# grillupboard.net
KiCad netlist of a schematic drawn in EAGLE
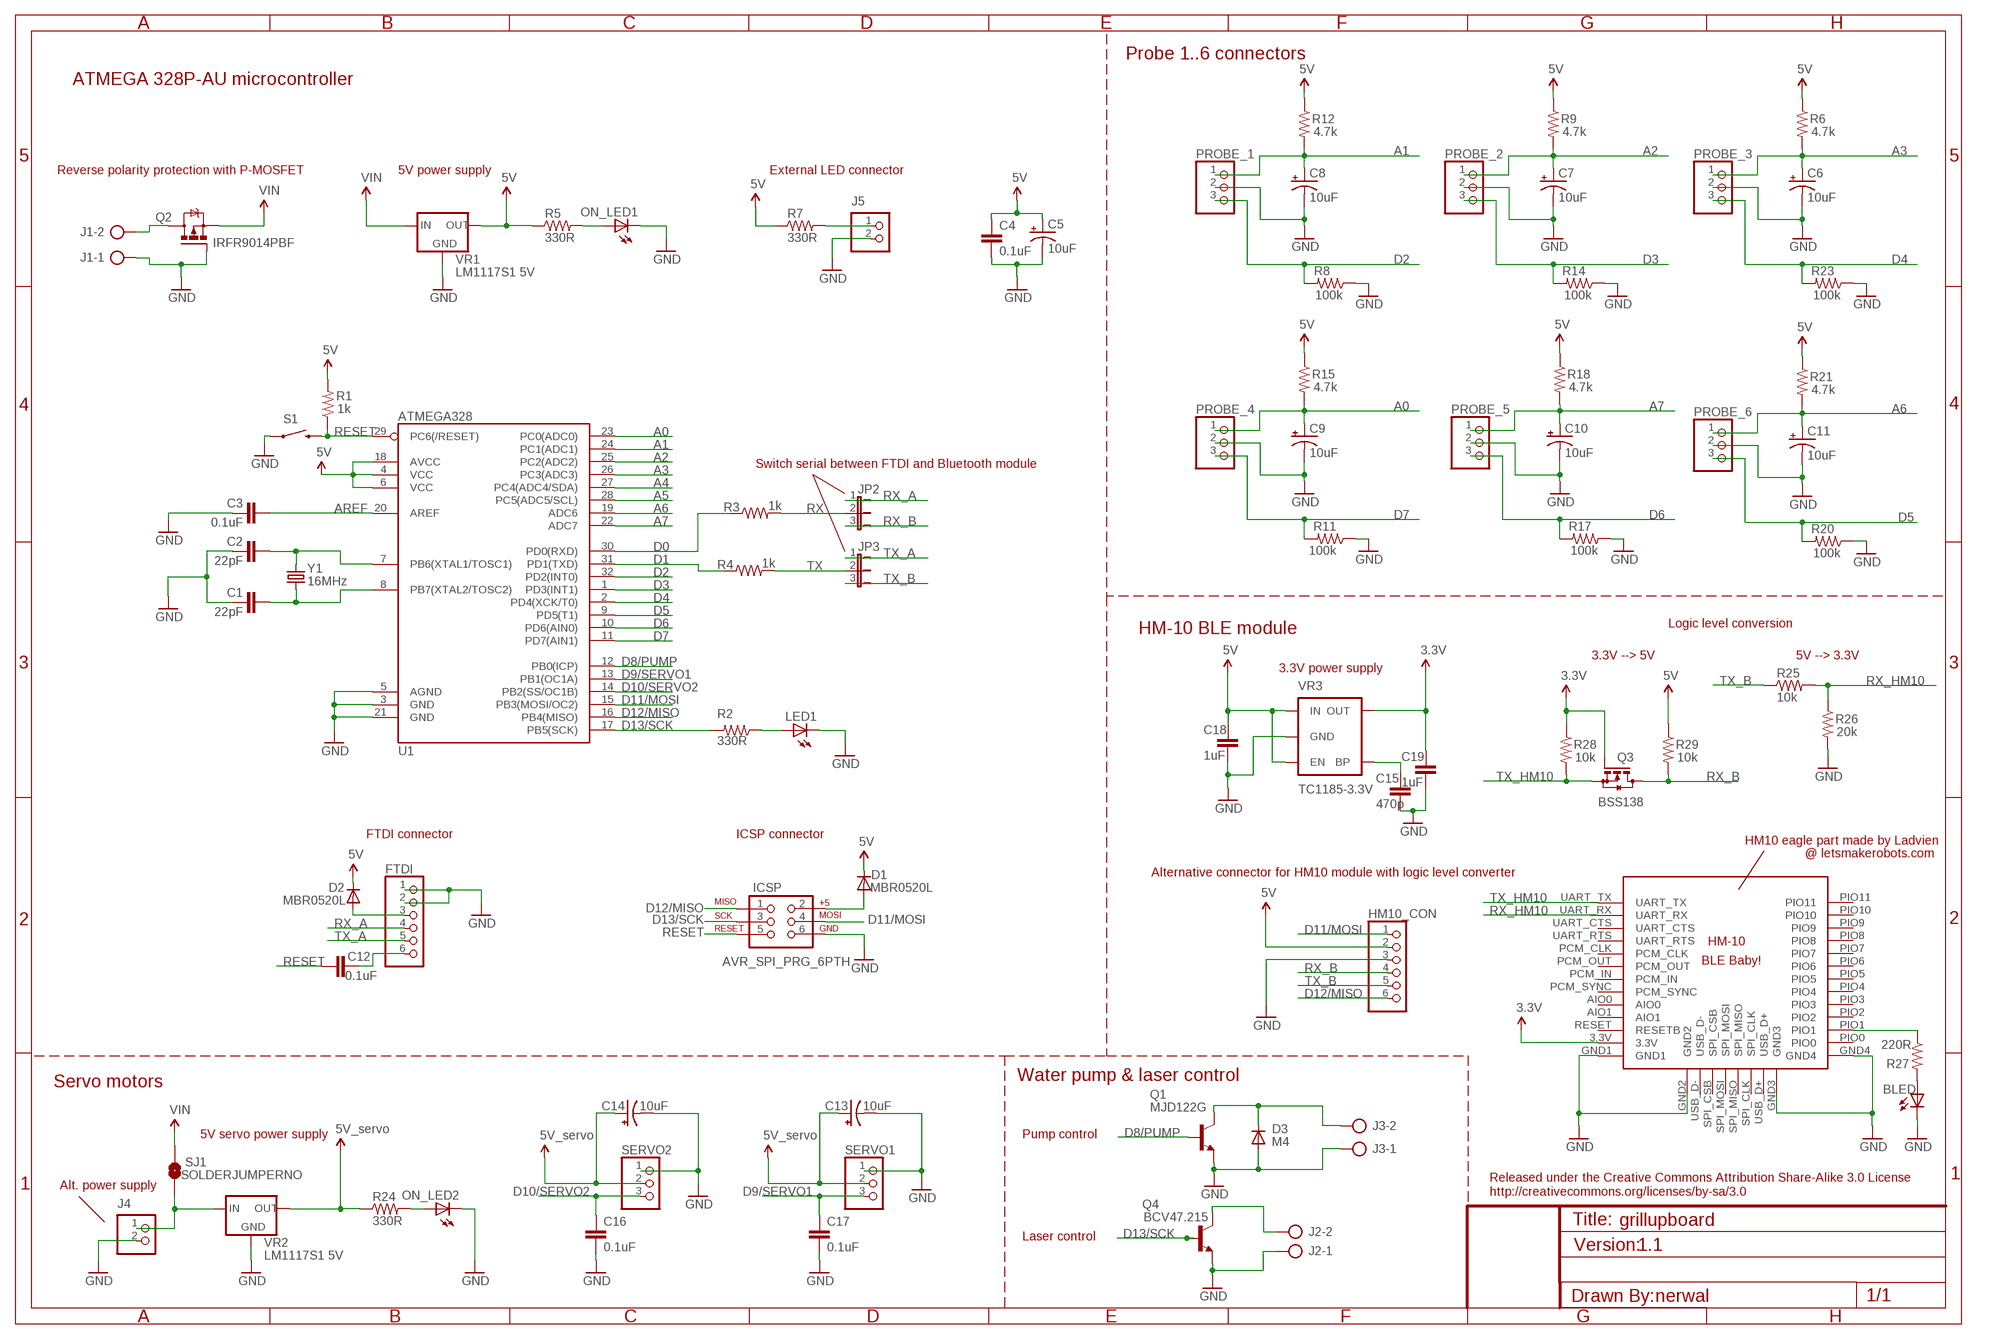
[diagram p0: schematic, sheet 1]

(export (version "E")
  (design (tool "Eeschema 10.0.6"))
  (components
    (comp (ref "BLED")
      (value "LED0603")
      (footprint "eagle-import:LED-0603")
      (libsource (lib "eagle-import") (part "LED0603"))
    )
    (comp (ref "C1")
      (value "22pF")
      (footprint "eagle-import:0805")
      (libsource (lib "eagle-import") (part "CAP0805"))
    )
    (comp (ref "C2")
      (value "22pF")
      (footprint "eagle-import:0805")
      (libsource (lib "eagle-import") (part "CAP0805"))
    )
    (comp (ref "C3")
      (value "0.1uF")
      (footprint "eagle-import:0805")
      (libsource (lib "eagle-import") (part "CAP0805"))
    )
    (comp (ref "C4")
      (value "0.1uF")
      (footprint "eagle-import:0805")
      (libsource (lib "eagle-import") (part "CAP0805"))
    )
    (comp (ref "C5")
      (value "10uF")
      (footprint "eagle-import:EIA3216")
      (libsource (lib "eagle-import") (part "CAP_POL1206"))
    )
    (comp (ref "C6")
      (value "10uF")
      (footprint "eagle-import:EIA3216")
      (libsource (lib "eagle-import") (part "CAP_POL1206"))
    )
    (comp (ref "C7")
      (value "10uF")
      (footprint "eagle-import:EIA3216")
      (libsource (lib "eagle-import") (part "CAP_POL1206"))
    )
    (comp (ref "C8")
      (value "10uF")
      (footprint "eagle-import:EIA3216")
      (libsource (lib "eagle-import") (part "CAP_POL1206"))
    )
    (comp (ref "C9")
      (value "10uF")
      (footprint "eagle-import:EIA3216")
      (libsource (lib "eagle-import") (part "CAP_POL1206"))
    )
    (comp (ref "C10")
      (value "10uF")
      (footprint "eagle-import:EIA3216")
      (libsource (lib "eagle-import") (part "CAP_POL1206"))
    )
    (comp (ref "C11")
      (value "10uF")
      (footprint "eagle-import:EIA3216")
      (libsource (lib "eagle-import") (part "CAP_POL1206"))
    )
    (comp (ref "C12")
      (value "0.1uF")
      (footprint "eagle-import:0805")
      (libsource (lib "eagle-import") (part "CAP0805"))
    )
    (comp (ref "C13")
      (value "10uF")
      (footprint "eagle-import:EIA3216")
      (libsource (lib "eagle-import") (part "CAP_POL1206"))
    )
    (comp (ref "C14")
      (value "10uF")
      (footprint "eagle-import:EIA3216")
      (libsource (lib "eagle-import") (part "CAP_POL1206"))
    )
    (comp (ref "C15")
      (value "470p")
      (footprint "eagle-import:0805")
      (libsource (lib "eagle-import") (part "CAP0805"))
    )
    (comp (ref "C16")
      (value "0.1uF")
      (footprint "eagle-import:0805")
      (libsource (lib "eagle-import") (part "CAP0805"))
    )
    (comp (ref "C17")
      (value "0.1uF")
      (footprint "eagle-import:0805")
      (libsource (lib "eagle-import") (part "CAP0805"))
    )
    (comp (ref "C18")
      (value "1uF")
      (footprint "eagle-import:0805")
      (libsource (lib "eagle-import") (part "CAP0805"))
    )
    (comp (ref "C19")
      (value "1uF")
      (footprint "eagle-import:0805")
      (libsource (lib "eagle-import") (part "CAP0805"))
    )
    (comp (ref "D1")
      (value "MBR0520L")
      (footprint "eagle-import:SOD123")
      (libsource (lib "eagle-import") (part "MBR0520LT"))
    )
    (comp (ref "D2")
      (value "MBR0520L")
      (footprint "eagle-import:SOD123")
      (libsource (lib "eagle-import") (part "MBR0520LT"))
    )
    (comp (ref "D3")
      (value "M4")
      (footprint "eagle-import:SMA-DIODE")
      (libsource (lib "eagle-import") (part "DIODESMA"))
    )
    (comp (ref "FTDI")
      (value "PINHD-1X6")
      (footprint "eagle-import:1X06")
      (libsource (lib "eagle-import") (part "PINHD-1X6"))
    )
    (comp (ref "HM10")
      (value "RANDOM_PARTS_BLE-HM-10")
      (footprint "eagle-import:RANDOM_PARTS_BLE-HM-10")
      (libsource (lib "eagle-import") (part "RANDOM_PARTS_BLE-HM-10"))
    )
    (comp (ref "HM10_CON")
      (value "PINHD-1X6")
      (footprint "eagle-import:1X06")
      (libsource (lib "eagle-import") (part "PINHD-1X6"))
    )
    (comp (ref "ICSP")
      (value "AVR_SPI_PRG_6PTH")
      (footprint "eagle-import:2X3")
      (libsource (lib "eagle-import") (part "AVR_SPI_PRG_6PTH"))
    )
    (comp (ref "J1")
      (value "AK500/2-H")
      (footprint "eagle-import:AK500_2-H")
      (libsource (lib "eagle-import") (part "AK500/2-H"))
    )
    (comp (ref "J2")
      (value "AK500/2-H")
      (footprint "eagle-import:AK500_2-H")
      (libsource (lib "eagle-import") (part "AK500/2-H"))
    )
    (comp (ref "J3")
      (value "AK500/2-H")
      (footprint "eagle-import:AK500_2-H")
      (libsource (lib "eagle-import") (part "AK500/2-H"))
    )
    (comp (ref "J4")
      (value "PINHD-1X2")
      (footprint "eagle-import:1X02")
      (libsource (lib "eagle-import") (part "PINHD-1X2"))
    )
    (comp (ref "J5")
      (value "PINHD-1X2")
      (footprint "eagle-import:1X02")
      (libsource (lib "eagle-import") (part "PINHD-1X2"))
    )
    (comp (ref "JP2")
      (value "JP2E")
      (footprint "eagle-import:JP2")
      (libsource (lib "eagle-import") (part "JP2E"))
    )
    (comp (ref "JP3")
      (value "JP2E")
      (footprint "eagle-import:JP2")
      (libsource (lib "eagle-import") (part "JP2E"))
    )
    (comp (ref "LED1")
      (value "LED0603")
      (footprint "eagle-import:LED-0603")
      (libsource (lib "eagle-import") (part "LED0603"))
    )
    (comp (ref "ON_LED1")
      (value "LED0603")
      (footprint "eagle-import:LED-0603")
      (libsource (lib "eagle-import") (part "LED0603"))
    )
    (comp (ref "ON_LED2")
      (value "LED0603")
      (footprint "eagle-import:LED-0603")
      (libsource (lib "eagle-import") (part "LED0603"))
    )
    (comp (ref "PROBE_1")
      (value "PINHD-1X3")
      (footprint "eagle-import:1X03")
      (libsource (lib "eagle-import") (part "PINHD-1X3"))
    )
    (comp (ref "PROBE_2")
      (value "PINHD-1X3")
      (footprint "eagle-import:1X03")
      (libsource (lib "eagle-import") (part "PINHD-1X3"))
    )
    (comp (ref "PROBE_3")
      (value "PINHD-1X3")
      (footprint "eagle-import:1X03")
      (libsource (lib "eagle-import") (part "PINHD-1X3"))
    )
    (comp (ref "PROBE_4")
      (value "PINHD-1X3")
      (footprint "eagle-import:1X03")
      (libsource (lib "eagle-import") (part "PINHD-1X3"))
    )
    (comp (ref "PROBE_5")
      (value "PINHD-1X3")
      (footprint "eagle-import:1X03")
      (libsource (lib "eagle-import") (part "PINHD-1X3"))
    )
    (comp (ref "PROBE_6")
      (value "PINHD-1X3")
      (footprint "eagle-import:1X03")
      (libsource (lib "eagle-import") (part "PINHD-1X3"))
    )
    (comp (ref "Q1")
      (value "MJD122G")
      (footprint "eagle-import:DPAK")
      (libsource (lib "eagle-import") (part "MJD31"))
    )
    (comp (ref "Q2")
      (value "IRFR9014PBF")
      (footprint "eagle-import:D-PAK_TO252AA")
      (libsource (lib "eagle-import") (part "IRF?5305R"))
    )
    (comp (ref "Q3")
      (value "BSS138")
      (footprint "eagle-import:SOT23")
      (libsource (lib "eagle-import") (part "BSS123"))
    )
    (comp (ref "Q4")
      (value "BCV47.215")
      (footprint "eagle-import:SOT23-BEC")
      (libsource (lib "eagle-import") (part "-NPN-SOT23-BECBCV71"))
    )
    (comp (ref "R1")
      (value "1k")
      (footprint "eagle-import:0805")
      (libsource (lib "eagle-import") (part "RESISTOR0805-RES"))
    )
    (comp (ref "R2")
      (value "330R")
      (footprint "eagle-import:0805")
      (libsource (lib "eagle-import") (part "RESISTOR0805-RES"))
    )
    (comp (ref "R3")
      (value "1k")
      (footprint "eagle-import:0805")
      (libsource (lib "eagle-import") (part "RESISTOR0805-RES"))
    )
    (comp (ref "R4")
      (value "1k")
      (footprint "eagle-import:0805")
      (libsource (lib "eagle-import") (part "RESISTOR0805-RES"))
    )
    (comp (ref "R5")
      (value "330R")
      (footprint "eagle-import:0805")
      (libsource (lib "eagle-import") (part "RESISTOR0805-RES"))
    )
    (comp (ref "R6")
      (value "4.7k")
      (footprint "eagle-import:0805")
      (libsource (lib "eagle-import") (part "RESISTOR0805-RES"))
    )
    (comp (ref "R7")
      (value "330R")
      (footprint "eagle-import:0805")
      (libsource (lib "eagle-import") (part "RESISTOR0805-RES"))
    )
    (comp (ref "R8")
      (value "100k")
      (footprint "eagle-import:0805")
      (libsource (lib "eagle-import") (part "RESISTOR0805-RES"))
    )
    (comp (ref "R9")
      (value "4.7k")
      (footprint "eagle-import:0805")
      (libsource (lib "eagle-import") (part "RESISTOR0805-RES"))
    )
    (comp (ref "R11")
      (value "100k")
      (footprint "eagle-import:0805")
      (libsource (lib "eagle-import") (part "RESISTOR0805-RES"))
    )
    (comp (ref "R12")
      (value "4.7k")
      (footprint "eagle-import:0805")
      (libsource (lib "eagle-import") (part "RESISTOR0805-RES"))
    )
    (comp (ref "R14")
      (value "100k")
      (footprint "eagle-import:0805")
      (libsource (lib "eagle-import") (part "RESISTOR0805-RES"))
    )
    (comp (ref "R15")
      (value "4.7k")
      (footprint "eagle-import:0805")
      (libsource (lib "eagle-import") (part "RESISTOR0805-RES"))
    )
    (comp (ref "R17")
      (value "100k")
      (footprint "eagle-import:0805")
      (libsource (lib "eagle-import") (part "RESISTOR0805-RES"))
    )
    (comp (ref "R18")
      (value "4.7k")
      (footprint "eagle-import:0805")
      (libsource (lib "eagle-import") (part "RESISTOR0805-RES"))
    )
    (comp (ref "R20")
      (value "100k")
      (footprint "eagle-import:0805")
      (libsource (lib "eagle-import") (part "RESISTOR0805-RES"))
    )
    (comp (ref "R21")
      (value "4.7k")
      (footprint "eagle-import:0805")
      (libsource (lib "eagle-import") (part "RESISTOR0805-RES"))
    )
    (comp (ref "R23")
      (value "100k")
      (footprint "eagle-import:0805")
      (libsource (lib "eagle-import") (part "RESISTOR0805-RES"))
    )
    (comp (ref "R24")
      (value "330R")
      (footprint "eagle-import:0805")
      (libsource (lib "eagle-import") (part "RESISTOR0805-RES"))
    )
    (comp (ref "R25")
      (value "10k")
      (footprint "eagle-import:0805")
      (libsource (lib "eagle-import") (part "RESISTOR0805-RES"))
    )
    (comp (ref "R26")
      (value "20k")
      (footprint "eagle-import:0805")
      (libsource (lib "eagle-import") (part "RESISTOR0805-RES"))
    )
    (comp (ref "R27")
      (value "220R")
      (footprint "eagle-import:0805")
      (libsource (lib "eagle-import") (part "RESISTOR0805-RES"))
    )
    (comp (ref "R28")
      (value "10k")
      (footprint "eagle-import:0805")
      (libsource (lib "eagle-import") (part "RESISTOR0805-RES"))
    )
    (comp (ref "R29")
      (value "10k")
      (footprint "eagle-import:0805")
      (libsource (lib "eagle-import") (part "RESISTOR0805-RES"))
    )
    (comp (ref "S1")
      (value "SWITCH-MOMENTARY-2-SMD-1101NE")
      (footprint "eagle-import:TACTILE-SWITCH-1101NE")
      (libsource (lib "eagle-import") (part "SWITCH-MOMENTARY-2-SMD-1101NE"))
    )
    (comp (ref "SERVO1")
      (value "PINHD-1X3")
      (footprint "eagle-import:1X03")
      (libsource (lib "eagle-import") (part "PINHD-1X3"))
    )
    (comp (ref "SERVO2")
      (value "PINHD-1X3")
      (footprint "eagle-import:1X03")
      (libsource (lib "eagle-import") (part "PINHD-1X3"))
    )
    (comp (ref "SJ1")
      (value "SOLDERJUMPERNO")
      (footprint "eagle-import:SJ_2S-NO")
      (libsource (lib "eagle-import") (part "SOLDERJUMPERNO"))
    )
    (comp (ref "U1")
      (value "ATMEGA328")
      (footprint "eagle-import:TQFP32-08")
      (libsource (lib "eagle-import") (part "ATMEGA168"))
    )
    (comp (ref "VR1")
      (value "LM1117S1 5V")
      (footprint "eagle-import:SOT223")
      (libsource (lib "eagle-import") (part "LM1117"))
    )
    (comp (ref "VR2")
      (value "LM1117S1 5V")
      (footprint "eagle-import:SOT223")
      (libsource (lib "eagle-import") (part "LM1117"))
    )
    (comp (ref "VR3")
      (value "TC1185-3.3V")
      (footprint "eagle-import:SOT23-5")
      (libsource (lib "eagle-import") (part "V_REG_LDOSMD"))
    )
    (comp (ref "Y1")
      (value "16MHz")
      (footprint "eagle-import:HC49_S")
      (libsource (lib "eagle-import") (part "CRYSTALHC49S"))
    )
  )
  (nets
    (net (code "1") (name "/A0") (class "Default")
      (node (ref "C9") (pin "A") (pinfunction "+_A") (pintype "passive"))
      (node (ref "PROBE_4") (pin "1") (pinfunction "1_1") (pintype "passive"))
      (node (ref "R15") (pin "2") (pinfunction "2_2") (pintype "passive"))
      (node (ref "U1") (pin "23") (pinfunction "PC0(ADC0)_23") (pintype "bidirectional"))
    )
    (net (code "2") (name "/A1") (class "Default")
      (node (ref "C8") (pin "A") (pinfunction "+_A") (pintype "passive"))
      (node (ref "PROBE_1") (pin "1") (pinfunction "1_1") (pintype "passive"))
      (node (ref "R12") (pin "2") (pinfunction "2_2") (pintype "passive"))
      (node (ref "U1") (pin "24") (pinfunction "PC1(ADC1)_24") (pintype "bidirectional"))
    )
    (net (code "3") (name "/A2") (class "Default")
      (node (ref "C7") (pin "A") (pinfunction "+_A") (pintype "passive"))
      (node (ref "PROBE_2") (pin "1") (pinfunction "1_1") (pintype "passive"))
      (node (ref "R9") (pin "2") (pinfunction "2_2") (pintype "passive"))
      (node (ref "U1") (pin "25") (pinfunction "PC2(ADC2)_25") (pintype "bidirectional"))
    )
    (net (code "4") (name "/A3") (class "Default")
      (node (ref "C6") (pin "A") (pinfunction "+_A") (pintype "passive"))
      (node (ref "PROBE_3") (pin "1") (pinfunction "1_1") (pintype "passive"))
      (node (ref "R6") (pin "2") (pinfunction "2_2") (pintype "passive"))
      (node (ref "U1") (pin "26") (pinfunction "PC3(ADC3)_26") (pintype "bidirectional"))
    )
    (net (code "5") (name "/A4") (class "Default")
      (node (ref "U1") (pin "27") (pinfunction "PC4(ADC4/SDA)_27") (pintype "bidirectional"))
    )
    (net (code "6") (name "/A5") (class "Default")
      (node (ref "U1") (pin "28") (pinfunction "PC5(ADC5/SCL)_28") (pintype "bidirectional"))
    )
    (net (code "7") (name "/A6") (class "Default")
      (node (ref "C11") (pin "A") (pinfunction "+_A") (pintype "passive"))
      (node (ref "PROBE_6") (pin "1") (pinfunction "1_1") (pintype "passive"))
      (node (ref "R21") (pin "2") (pinfunction "2_2") (pintype "passive"))
      (node (ref "U1") (pin "19") (pinfunction "ADC6_19") (pintype "bidirectional"))
    )
    (net (code "8") (name "/A7") (class "Default")
      (node (ref "C10") (pin "A") (pinfunction "+_A") (pintype "passive"))
      (node (ref "PROBE_5") (pin "1") (pinfunction "1_1") (pintype "passive"))
      (node (ref "R18") (pin "2") (pinfunction "2_2") (pintype "passive"))
      (node (ref "U1") (pin "22") (pinfunction "ADC7_22") (pintype "bidirectional"))
    )
    (net (code "9") (name "/AREF") (class "Default")
      (node (ref "C3") (pin "2") (pinfunction "2_2") (pintype "passive"))
      (node (ref "U1") (pin "20") (pinfunction "AREF_20") (pintype "bidirectional"))
    )
    (net (code "10") (name "/D0") (class "Default")
      (node (ref "R3") (pin "1") (pinfunction "1_1") (pintype "passive"))
      (node (ref "U1") (pin "30") (pinfunction "PD0(RXD)_30") (pintype "bidirectional"))
    )
    (net (code "11") (name "/D1") (class "Default")
      (node (ref "R4") (pin "1") (pinfunction "1_1") (pintype "passive"))
      (node (ref "U1") (pin "31") (pinfunction "PD1(TXD)_31") (pintype "bidirectional"))
    )
    (net (code "12") (name "/D2") (class "Default")
      (node (ref "PROBE_1") (pin "3") (pinfunction "3_3") (pintype "passive"))
      (node (ref "R8") (pin "2") (pinfunction "2_2") (pintype "passive"))
      (node (ref "U1") (pin "32") (pinfunction "PD2(INT0)_32") (pintype "bidirectional"))
    )
    (net (code "13") (name "/D3") (class "Default")
      (node (ref "PROBE_2") (pin "3") (pinfunction "3_3") (pintype "passive"))
      (node (ref "R14") (pin "2") (pinfunction "2_2") (pintype "passive"))
      (node (ref "U1") (pin "1") (pinfunction "PD3(INT1)_1") (pintype "bidirectional"))
    )
    (net (code "14") (name "/D4") (class "Default")
      (node (ref "PROBE_3") (pin "3") (pinfunction "3_3") (pintype "passive"))
      (node (ref "R23") (pin "2") (pinfunction "2_2") (pintype "passive"))
      (node (ref "U1") (pin "2") (pinfunction "PD4(XCK/T0)_2") (pintype "bidirectional"))
    )
    (net (code "15") (name "/D5") (class "Default")
      (node (ref "PROBE_6") (pin "3") (pinfunction "3_3") (pintype "passive"))
      (node (ref "R20") (pin "2") (pinfunction "2_2") (pintype "passive"))
      (node (ref "U1") (pin "9") (pinfunction "PD5(T1)_9") (pintype "bidirectional"))
    )
    (net (code "16") (name "/D6") (class "Default")
      (node (ref "PROBE_5") (pin "3") (pinfunction "3_3") (pintype "passive"))
      (node (ref "R17") (pin "2") (pinfunction "2_2") (pintype "passive"))
      (node (ref "U1") (pin "10") (pinfunction "PD6(AIN0)_10") (pintype "bidirectional"))
    )
    (net (code "17") (name "/D7") (class "Default")
      (node (ref "PROBE_4") (pin "3") (pinfunction "3_3") (pintype "passive"))
      (node (ref "R11") (pin "2") (pinfunction "2_2") (pintype "passive"))
      (node (ref "U1") (pin "11") (pinfunction "PD7(AIN1)_11") (pintype "bidirectional"))
    )
    (net (code "18") (name "/D8{slash}PUMP") (class "Default")
      (node (ref "Q1") (pin "1") (pinfunction "B_1") (pintype "passive"))
      (node (ref "U1") (pin "12") (pinfunction "PB0(ICP)_12") (pintype "bidirectional"))
    )
    (net (code "19") (name "/D9{slash}SERVO1") (class "Default")
      (node (ref "C17") (pin "1") (pinfunction "1_1") (pintype "passive"))
      (node (ref "SERVO1") (pin "3") (pinfunction "3_3") (pintype "passive"))
      (node (ref "U1") (pin "13") (pinfunction "PB1(OC1A)_13") (pintype "bidirectional"))
    )
    (net (code "20") (name "/D10{slash}SERVO2") (class "Default")
      (node (ref "C16") (pin "1") (pinfunction "1_1") (pintype "passive"))
      (node (ref "SERVO2") (pin "3") (pinfunction "3_3") (pintype "passive"))
      (node (ref "U1") (pin "14") (pinfunction "PB2(SS/OC1B)_14") (pintype "bidirectional"))
    )
    (net (code "21") (name "/D11{slash}MOSI") (class "Default")
      (node (ref "HM10_CON") (pin "1") (pinfunction "1_1") (pintype "passive"))
      (node (ref "ICSP") (pin "4") (pinfunction "4_4") (pintype "passive"))
      (node (ref "U1") (pin "15") (pinfunction "PB3(MOSI/OC2)_15") (pintype "bidirectional"))
    )
    (net (code "22") (name "/D12{slash}MISO") (class "Default")
      (node (ref "HM10_CON") (pin "6") (pinfunction "6_6") (pintype "passive"))
      (node (ref "ICSP") (pin "1") (pinfunction "1_1") (pintype "passive"))
      (node (ref "U1") (pin "16") (pinfunction "PB4(MISO)_16") (pintype "bidirectional"))
    )
    (net (code "23") (name "/D13{slash}SCK") (class "Default")
      (node (ref "ICSP") (pin "3") (pinfunction "3_3") (pintype "passive"))
      (node (ref "Q4") (pin "B") (pinfunction "B_B") (pintype "passive"))
      (node (ref "R2") (pin "2") (pinfunction "2_2") (pintype "passive"))
      (node (ref "U1") (pin "17") (pinfunction "PB5(SCK)_17") (pintype "bidirectional"))
    )
    (net (code "24") (name "/RESET") (class "Default")
      (node (ref "C12") (pin "1") (pinfunction "1_1") (pintype "passive"))
      (node (ref "ICSP") (pin "5") (pinfunction "5_5") (pintype "passive"))
      (node (ref "R1") (pin "1") (pinfunction "1_1") (pintype "passive"))
      (node (ref "S1") (pin "P$2") (pinfunction "2_P$2") (pintype "passive"))
      (node (ref "U1") (pin "29") (pinfunction "PC6(/RESET)_29") (pintype "bidirectional"))
    )
    (net (code "25") (name "/RX") (class "Default")
      (node (ref "JP2") (pin "2") (pinfunction "2_2") (pintype "passive"))
      (node (ref "R3") (pin "2") (pinfunction "2_2") (pintype "passive"))
    )
    (net (code "26") (name "/RX_A") (class "Default")
      (node (ref "FTDI") (pin "4") (pinfunction "4_4") (pintype "passive"))
      (node (ref "JP2") (pin "1") (pinfunction "1_1") (pintype "passive"))
    )
    (net (code "27") (name "/RX_B") (class "Default")
      (node (ref "HM10_CON") (pin "4") (pinfunction "4_4") (pintype "passive"))
      (node (ref "JP2") (pin "3") (pinfunction "3_3") (pintype "passive"))
      (node (ref "Q3") (pin "3") (pinfunction "D_3") (pintype "passive"))
      (node (ref "R29") (pin "2") (pinfunction "2_2") (pintype "passive"))
    )
    (net (code "28") (name "/RX_HM10") (class "Default")
      (node (ref "HM10") (pin "UART_RX") (pinfunction "UART_RX_UART_RX") (pintype "bidirectional"))
      (node (ref "R25") (pin "2") (pinfunction "2_2") (pintype "passive"))
      (node (ref "R26") (pin "1") (pinfunction "1_1") (pintype "passive"))
    )
    (net (code "29") (name "/TX") (class "Default")
      (node (ref "JP3") (pin "2") (pinfunction "2_2") (pintype "passive"))
      (node (ref "R4") (pin "2") (pinfunction "2_2") (pintype "passive"))
    )
    (net (code "30") (name "/TX_A") (class "Default")
      (node (ref "FTDI") (pin "5") (pinfunction "5_5") (pintype "passive"))
      (node (ref "JP3") (pin "1") (pinfunction "1_1") (pintype "passive"))
    )
    (net (code "31") (name "/TX_B") (class "Default")
      (node (ref "HM10_CON") (pin "5") (pinfunction "5_5") (pintype "passive"))
      (node (ref "JP3") (pin "3") (pinfunction "3_3") (pintype "passive"))
      (node (ref "R25") (pin "1") (pinfunction "1_1") (pintype "passive"))
    )
    (net (code "32") (name "/TX_HM10") (class "Default")
      (node (ref "HM10") (pin "UART_TX") (pinfunction "UART_TX_UART_TX") (pintype "bidirectional"))
      (node (ref "Q3") (pin "2") (pinfunction "S_2") (pintype "passive"))
      (node (ref "R28") (pin "2") (pinfunction "2_2") (pintype "passive"))
    )
    (net (code "33") (name "3.3V") (class "Default")
      (node (ref "C19") (pin "1") (pinfunction "1_1") (pintype "passive"))
      (node (ref "HM10") (pin "3.3V") (pinfunction "3.3V_3.3V") (pintype "bidirectional"))
      (node (ref "Q3") (pin "1") (pinfunction "G_1") (pintype "passive"))
      (node (ref "R28") (pin "1") (pinfunction "1_1") (pintype "passive"))
      (node (ref "VR3") (pin "5") (pinfunction "OUT_5") (pintype "passive"))
    )
    (net (code "34") (name "5V") (class "Default")
      (node (ref "C18") (pin "1") (pinfunction "1_1") (pintype "passive"))
      (node (ref "C4") (pin "1") (pinfunction "1_1") (pintype "passive"))
      (node (ref "C5") (pin "A") (pinfunction "+_A") (pintype "passive"))
      (node (ref "D1") (pin "C") (pinfunction "C_C") (pintype "passive"))
      (node (ref "D2") (pin "C") (pinfunction "C_C") (pintype "passive"))
      (node (ref "HM10_CON") (pin "2") (pinfunction "2_2") (pintype "passive"))
      (node (ref "R1") (pin "2") (pinfunction "2_2") (pintype "passive"))
      (node (ref "R12") (pin "1") (pinfunction "1_1") (pintype "passive"))
      (node (ref "R15") (pin "1") (pinfunction "1_1") (pintype "passive"))
      (node (ref "R18") (pin "1") (pinfunction "1_1") (pintype "passive"))
      (node (ref "R21") (pin "1") (pinfunction "1_1") (pintype "passive"))
      (node (ref "R29") (pin "1") (pinfunction "1_1") (pintype "passive"))
      (node (ref "R5") (pin "1") (pinfunction "1_1") (pintype "passive"))
      (node (ref "R6") (pin "1") (pinfunction "1_1") (pintype "passive"))
      (node (ref "R7") (pin "1") (pinfunction "1_1") (pintype "passive"))
      (node (ref "R9") (pin "1") (pinfunction "1_1") (pintype "passive"))
      (node (ref "U1") (pin "18") (pinfunction "AVCC_18") (pintype "bidirectional"))
      (node (ref "U1") (pin "4") (pinfunction "VCC_4") (pintype "bidirectional"))
      (node (ref "U1") (pin "6") (pinfunction "VCC_6") (pintype "bidirectional"))
      (node (ref "VR1") (pin "2") (pinfunction "OUT_2") (pintype "passive"))
      (node (ref "VR3") (pin "1") (pinfunction "IN_1") (pintype "input"))
      (node (ref "VR3") (pin "3") (pinfunction "EN_3") (pintype "input"))
    )
    (net (code "35") (name "5V_servo") (class "Default")
      (node (ref "C13") (pin "A") (pinfunction "+_A") (pintype "passive"))
      (node (ref "C14") (pin "A") (pinfunction "+_A") (pintype "passive"))
      (node (ref "R24") (pin "1") (pinfunction "1_1") (pintype "passive"))
      (node (ref "SERVO1") (pin "2") (pinfunction "2_2") (pintype "passive"))
      (node (ref "SERVO2") (pin "2") (pinfunction "2_2") (pintype "passive"))
      (node (ref "VR2") (pin "2") (pinfunction "OUT_2") (pintype "passive"))
    )
    (net (code "36") (name "GND") (class "Default")
      (node (ref "BLED") (pin "C") (pinfunction "C_C") (pintype "passive"))
      (node (ref "C1") (pin "1") (pinfunction "1_1") (pintype "passive"))
      (node (ref "C10") (pin "C") (pinfunction "-_C") (pintype "passive"))
      (node (ref "C11") (pin "C") (pinfunction "-_C") (pintype "passive"))
      (node (ref "C13") (pin "C") (pinfunction "-_C") (pintype "passive"))
      (node (ref "C14") (pin "C") (pinfunction "-_C") (pintype "passive"))
      (node (ref "C15") (pin "2") (pinfunction "2_2") (pintype "passive"))
      (node (ref "C16") (pin "2") (pinfunction "2_2") (pintype "passive"))
      (node (ref "C17") (pin "2") (pinfunction "2_2") (pintype "passive"))
      (node (ref "C18") (pin "2") (pinfunction "2_2") (pintype "passive"))
      (node (ref "C19") (pin "2") (pinfunction "2_2") (pintype "passive"))
      (node (ref "C2") (pin "1") (pinfunction "1_1") (pintype "passive"))
      (node (ref "C3") (pin "1") (pinfunction "1_1") (pintype "passive"))
      (node (ref "C4") (pin "2") (pinfunction "2_2") (pintype "passive"))
      (node (ref "C5") (pin "C") (pinfunction "-_C") (pintype "passive"))
      (node (ref "C6") (pin "C") (pinfunction "-_C") (pintype "passive"))
      (node (ref "C7") (pin "C") (pinfunction "-_C") (pintype "passive"))
      (node (ref "C8") (pin "C") (pinfunction "-_C") (pintype "passive"))
      (node (ref "C9") (pin "C") (pinfunction "-_C") (pintype "passive"))
      (node (ref "D3") (pin "A") (pinfunction "A_A") (pintype "passive"))
      (node (ref "FTDI") (pin "1") (pinfunction "1_1") (pintype "passive"))
      (node (ref "FTDI") (pin "2") (pinfunction "2_2") (pintype "passive"))
      (node (ref "HM10") (pin "GND1") (pinfunction "GND1_GND1") (pintype "bidirectional"))
      (node (ref "HM10") (pin "GND2") (pinfunction "GND2_GND2") (pintype "bidirectional"))
      (node (ref "HM10") (pin "GND3") (pinfunction "GND3_GND3") (pintype "bidirectional"))
      (node (ref "HM10") (pin "GND4") (pinfunction "GND4_GND4") (pintype "bidirectional"))
      (node (ref "HM10_CON") (pin "3") (pinfunction "3_3") (pintype "passive"))
      (node (ref "ICSP") (pin "6") (pinfunction "6_6") (pintype "passive"))
      (node (ref "J1") (pin "1") (pinfunction "KL_1") (pintype "passive"))
      (node (ref "J2") (pin "1") (pinfunction "KL_1") (pintype "passive"))
      (node (ref "J3") (pin "1") (pinfunction "KL_1") (pintype "passive"))
      (node (ref "J4") (pin "2") (pinfunction "2_2") (pintype "passive"))
      (node (ref "J5") (pin "2") (pinfunction "2_2") (pintype "passive"))
      (node (ref "LED1") (pin "C") (pinfunction "C_C") (pintype "passive"))
      (node (ref "ON_LED1") (pin "C") (pinfunction "C_C") (pintype "passive"))
      (node (ref "ON_LED2") (pin "C") (pinfunction "C_C") (pintype "passive"))
      (node (ref "PROBE_1") (pin "2") (pinfunction "2_2") (pintype "passive"))
      (node (ref "PROBE_2") (pin "2") (pinfunction "2_2") (pintype "passive"))
      (node (ref "PROBE_3") (pin "2") (pinfunction "2_2") (pintype "passive"))
      (node (ref "PROBE_4") (pin "2") (pinfunction "2_2") (pintype "passive"))
      (node (ref "PROBE_5") (pin "2") (pinfunction "2_2") (pintype "passive"))
      (node (ref "PROBE_6") (pin "2") (pinfunction "2_2") (pintype "passive"))
      (node (ref "Q1") (pin "3") (pinfunction "E_3") (pintype "passive"))
      (node (ref "Q2") (pin "1") (pinfunction "G_1") (pintype "passive"))
      (node (ref "Q4") (pin "E") (pinfunction "E_E") (pintype "passive"))
      (node (ref "R11") (pin "1") (pinfunction "1_1") (pintype "passive"))
      (node (ref "R14") (pin "1") (pinfunction "1_1") (pintype "passive"))
      (node (ref "R17") (pin "1") (pinfunction "1_1") (pintype "passive"))
      (node (ref "R20") (pin "1") (pinfunction "1_1") (pintype "passive"))
      (node (ref "R23") (pin "1") (pinfunction "1_1") (pintype "passive"))
      (node (ref "R26") (pin "2") (pinfunction "2_2") (pintype "passive"))
      (node (ref "R8") (pin "1") (pinfunction "1_1") (pintype "passive"))
      (node (ref "S1") (pin "P$1") (pinfunction "1_P$1") (pintype "passive"))
      (node (ref "SERVO1") (pin "1") (pinfunction "1_1") (pintype "passive"))
      (node (ref "SERVO2") (pin "1") (pinfunction "1_1") (pintype "passive"))
      (node (ref "U1") (pin "21") (pinfunction "GND_21") (pintype "bidirectional"))
      (node (ref "U1") (pin "3") (pinfunction "GND_3") (pintype "bidirectional"))
      (node (ref "U1") (pin "5") (pinfunction "AGND_5") (pintype "bidirectional"))
      (node (ref "VR1") (pin "1") (pinfunction "GND_1") (pintype "input"))
      (node (ref "VR2") (pin "1") (pinfunction "GND_1") (pintype "input"))
      (node (ref "VR3") (pin "2") (pinfunction "GND_2") (pintype "input"))
    )
    (net (code "37") (name "Net-(BLED-PadA)") (class "Default")
      (node (ref "BLED") (pin "A") (pinfunction "A_A") (pintype "passive"))
      (node (ref "R27") (pin "2") (pinfunction "2_2") (pintype "passive"))
    )
    (net (code "38") (name "Net-(C12-Pad2)") (class "Default")
      (node (ref "C12") (pin "2") (pinfunction "2_2") (pintype "passive"))
      (node (ref "FTDI") (pin "6") (pinfunction "6_6") (pintype "passive"))
    )
    (net (code "39") (name "Net-(D1-PadA)") (class "Default")
      (node (ref "D1") (pin "A") (pinfunction "A_A") (pintype "passive"))
      (node (ref "ICSP") (pin "2") (pinfunction "2_2") (pintype "passive"))
    )
    (net (code "40") (name "Net-(D2-PadA)") (class "Default")
      (node (ref "D2") (pin "A") (pinfunction "A_A") (pintype "passive"))
      (node (ref "FTDI") (pin "3") (pinfunction "3_3") (pintype "passive"))
    )
    (net (code "41") (name "Net-(HM10-PadPIO1)") (class "Default")
      (node (ref "HM10") (pin "PIO1") (pinfunction "PIO1_PIO1") (pintype "bidirectional"))
      (node (ref "R27") (pin "1") (pinfunction "1_1") (pintype "passive"))
    )
    (net (code "42") (name "Net-(J1B-KL)") (class "Default")
      (node (ref "J1") (pin "2") (pinfunction "KL_2") (pintype "passive"))
      (node (ref "Q2") (pin "4") (pinfunction "D_4") (pintype "passive"))
    )
    (net (code "43") (name "Net-(J2B-KL)") (class "Default")
      (node (ref "J2") (pin "2") (pinfunction "KL_2") (pintype "passive"))
      (node (ref "Q4") (pin "C") (pinfunction "C_C") (pintype "passive"))
    )
    (net (code "44") (name "Net-(J3B-KL)") (class "Default")
      (node (ref "D3") (pin "C") (pinfunction "C_C") (pintype "passive"))
      (node (ref "J3") (pin "2") (pinfunction "KL_2") (pintype "passive"))
      (node (ref "Q1") (pin "4") (pinfunction "C_4") (pintype "passive"))
    )
    (net (code "45") (name "Net-(J5-Pad1)") (class "Default")
      (node (ref "J5") (pin "1") (pinfunction "1_1") (pintype "passive"))
      (node (ref "R7") (pin "2") (pinfunction "2_2") (pintype "passive"))
    )
    (net (code "46") (name "Net-(LED1-PadA)") (class "Default")
      (node (ref "LED1") (pin "A") (pinfunction "A_A") (pintype "passive"))
      (node (ref "R2") (pin "1") (pinfunction "1_1") (pintype "passive"))
    )
    (net (code "47") (name "Net-(ON_LED1-PadA)") (class "Default")
      (node (ref "ON_LED1") (pin "A") (pinfunction "A_A") (pintype "passive"))
      (node (ref "R5") (pin "2") (pinfunction "2_2") (pintype "passive"))
    )
    (net (code "48") (name "Net-(ON_LED2-PadA)") (class "Default")
      (node (ref "ON_LED2") (pin "A") (pinfunction "A_A") (pintype "passive"))
      (node (ref "R24") (pin "2") (pinfunction "2_2") (pintype "passive"))
    )
    (net (code "49") (name "Net-(U1-PB6(XTAL1{slash}TOSC1))") (class "Default")
      (node (ref "C2") (pin "2") (pinfunction "2_2") (pintype "passive"))
      (node (ref "U1") (pin "7") (pinfunction "PB6(XTAL1/TOSC1)_7") (pintype "bidirectional"))
      (node (ref "Y1") (pin "2") (pinfunction "2_2") (pintype "passive"))
    )
    (net (code "50") (name "Net-(U1-PB7(XTAL2{slash}TOSC2))") (class "Default")
      (node (ref "C1") (pin "2") (pinfunction "2_2") (pintype "passive"))
      (node (ref "U1") (pin "8") (pinfunction "PB7(XTAL2/TOSC2)_8") (pintype "bidirectional"))
      (node (ref "Y1") (pin "1") (pinfunction "1_1") (pintype "passive"))
    )
    (net (code "51") (name "Net-(VR2-IN)") (class "Default")
      (node (ref "J4") (pin "1") (pinfunction "1_1") (pintype "passive"))
      (node (ref "SJ1") (pin "1") (pinfunction "1_1") (pintype "passive"))
      (node (ref "VR2") (pin "3") (pinfunction "IN_3") (pintype "input"))
    )
    (net (code "52") (name "Net-(VR3-BP)") (class "Default")
      (node (ref "C15") (pin "1") (pinfunction "1_1") (pintype "passive"))
      (node (ref "VR3") (pin "4") (pinfunction "BP_4") (pintype "input"))
    )
    (net (code "53") (name "VIN") (class "Default")
      (node (ref "Q2") (pin "3") (pinfunction "S_3") (pintype "passive"))
      (node (ref "SJ1") (pin "2") (pinfunction "2_2") (pintype "passive"))
      (node (ref "VR1") (pin "3") (pinfunction "IN_3") (pintype "input"))
    )
    (net (code "54") (name "unconnected-(HM10-PadAIO0)") (class "Default")
      (node (ref "HM10") (pin "AIO0") (pinfunction "AIO0_AIO0") (pintype "bidirectional"))
    )
    (net (code "55") (name "unconnected-(HM10-PadAIO1)") (class "Default")
      (node (ref "HM10") (pin "AIO1") (pinfunction "AIO1_AIO1") (pintype "bidirectional"))
    )
    (net (code "56") (name "unconnected-(HM10-PadPCM_CLK)") (class "Default")
      (node (ref "HM10") (pin "PCM_CLK") (pinfunction "PCM_CLK_PCM_CLK") (pintype "bidirectional"))
    )
    (net (code "57") (name "unconnected-(HM10-PadPCM_IN)") (class "Default")
      (node (ref "HM10") (pin "PCM_IN") (pinfunction "PCM_IN_PCM_IN") (pintype "bidirectional"))
    )
    (net (code "58") (name "unconnected-(HM10-PadPCM_OUT)") (class "Default")
      (node (ref "HM10") (pin "PCM_OUT") (pinfunction "PCM_OUT_PCM_OUT") (pintype "bidirectional"))
    )
    (net (code "59") (name "unconnected-(HM10-PadPCM_SYNC)") (class "Default")
      (node (ref "HM10") (pin "PCM_SYNC") (pinfunction "PCM_SYNC_PCM_SYNC") (pintype "bidirectional"))
    )
    (net (code "60") (name "unconnected-(HM10-PadPIO0)") (class "Default")
      (node (ref "HM10") (pin "PIO0") (pinfunction "PIO0_PIO0") (pintype "bidirectional"))
    )
    (net (code "61") (name "unconnected-(HM10-PadPIO2)") (class "Default")
      (node (ref "HM10") (pin "PIO2") (pinfunction "PIO2_PIO2") (pintype "bidirectional"))
    )
    (net (code "62") (name "unconnected-(HM10-PadPIO3)") (class "Default")
      (node (ref "HM10") (pin "PIO3") (pinfunction "PIO3_PIO3") (pintype "bidirectional"))
    )
    (net (code "63") (name "unconnected-(HM10-PadPIO4)") (class "Default")
      (node (ref "HM10") (pin "PIO4") (pinfunction "PIO4_PIO4") (pintype "bidirectional"))
    )
    (net (code "64") (name "unconnected-(HM10-PadPIO5)") (class "Default")
      (node (ref "HM10") (pin "PIO5") (pinfunction "PIO5_PIO5") (pintype "bidirectional"))
    )
    (net (code "65") (name "unconnected-(HM10-PadPIO6)") (class "Default")
      (node (ref "HM10") (pin "PIO6") (pinfunction "PIO6_PIO6") (pintype "bidirectional"))
    )
    (net (code "66") (name "unconnected-(HM10-PadPIO7)") (class "Default")
      (node (ref "HM10") (pin "PIO7") (pinfunction "PIO7_PIO7") (pintype "bidirectional"))
    )
    (net (code "67") (name "unconnected-(HM10-PadPIO8)") (class "Default")
      (node (ref "HM10") (pin "PIO8") (pinfunction "PIO8_PIO8") (pintype "bidirectional"))
    )
    (net (code "68") (name "unconnected-(HM10-PadPIO9)") (class "Default")
      (node (ref "HM10") (pin "PIO9") (pinfunction "PIO9_PIO9") (pintype "bidirectional"))
    )
    (net (code "69") (name "unconnected-(HM10-PadPIO10)") (class "Default")
      (node (ref "HM10") (pin "PIO10") (pinfunction "PIO10_PIO10") (pintype "bidirectional"))
    )
    (net (code "70") (name "unconnected-(HM10-PadPIO11)") (class "Default")
      (node (ref "HM10") (pin "PIO11") (pinfunction "PIO11_PIO11") (pintype "bidirectional"))
    )
    (net (code "71") (name "unconnected-(HM10-PadSPI_CLK)") (class "Default")
      (node (ref "HM10") (pin "SPI_CLK") (pinfunction "SPI_CLK_SPI_CLK") (pintype "bidirectional"))
    )
    (net (code "72") (name "unconnected-(HM10-PadSPI_CSB)") (class "Default")
      (node (ref "HM10") (pin "SPI_CSB") (pinfunction "SPI_CSB_SPI_CSB") (pintype "bidirectional"))
    )
    (net (code "73") (name "unconnected-(HM10-PadSPI_MISO)") (class "Default")
      (node (ref "HM10") (pin "SPI_MISO") (pinfunction "SPI_MISO_SPI_MISO") (pintype "bidirectional"))
    )
    (net (code "74") (name "unconnected-(HM10-PadSPI_MOSI)") (class "Default")
      (node (ref "HM10") (pin "SPI_MOSI") (pinfunction "SPI_MOSI_SPI_MOSI") (pintype "bidirectional"))
    )
    (net (code "75") (name "unconnected-(HM10-PadUART_CTS)") (class "Default")
      (node (ref "HM10") (pin "UART_CTS") (pinfunction "UART_CTS_UART_CTS") (pintype "bidirectional"))
    )
    (net (code "76") (name "unconnected-(HM10-PadUART_RTS)") (class "Default")
      (node (ref "HM10") (pin "UART_RTS") (pinfunction "UART_RTS_UART_RTS") (pintype "bidirectional"))
    )
    (net (code "77") (name "unconnected-(HM10-PadUSB_D+)") (class "Default")
      (node (ref "HM10") (pin "USB_D+") (pinfunction "USB_D+_USB_D+") (pintype "bidirectional"))
    )
    (net (code "78") (name "unconnected-(HM10-PadUSB_D-)") (class "Default")
      (node (ref "HM10") (pin "USB_D-") (pinfunction "USB_D-_USB_D-") (pintype "bidirectional"))
    )
    (net (code "79") (name "unconnected-(HM10-RESETB-PadRESET)") (class "Default")
      (node (ref "HM10") (pin "RESET") (pinfunction "RESETB_RESET") (pintype "bidirectional"))
    )
  )
)
